# BUTTONs.net
KiCad netlist of a schematic drawn in Altium Designer
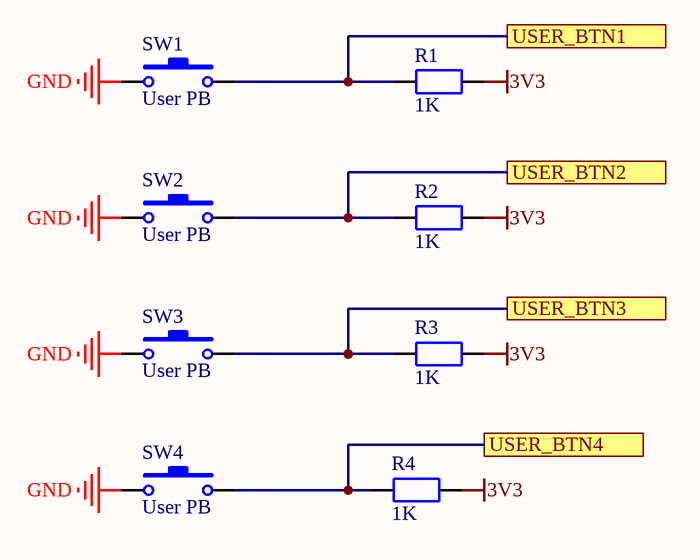
[diagram p0: BUTTONs.SchDoc]

(export (version "E")
  (design (tool "Eeschema 10.0.6"))
  (components
    (comp (ref "R1")
      (value "1K")
      (footprint "0402_RES")
      (description "Resistor")
      (libsource (lib "Lib3D_Altium10_Schlib") (part "RES"))
    )
    (comp (ref "R2")
      (value "1K")
      (footprint "0402_RES")
      (description "Resistor")
      (libsource (lib "Lib3D_Altium10_Schlib") (part "RES"))
    )
    (comp (ref "R3")
      (value "1K")
      (footprint "0402_RES")
      (description "Resistor")
      (libsource (lib "Lib3D_Altium10_Schlib") (part "RES"))
    )
    (comp (ref "R4")
      (value "1K")
      (footprint "0402_RES")
      (description "Resistor")
      (libsource (lib "Lib3D_Altium10_Schlib") (part "RES"))
    )
    (comp (ref "SW1")
      (value "User PB")
      (footprint "SW-PB SMD KMR2")
      (description "Push-button SMD")
      (libsource (lib "ST_Lib3D") (part "SW-PB_1"))
    )
    (comp (ref "SW2")
      (value "User PB")
      (footprint "SW-PB SMD KMR2")
      (description "Push-button SMD")
      (libsource (lib "ST_Lib3D") (part "SW-PB_1"))
    )
    (comp (ref "SW3")
      (value "User PB")
      (footprint "SW-PB SMD KMR2")
      (description "Push-button SMD")
      (libsource (lib "ST_Lib3D") (part "SW-PB_1"))
    )
    (comp (ref "SW4")
      (value "User PB")
      (footprint "SW-PB SMD KMR2")
      (description "Push-button SMD")
      (libsource (lib "ST_Lib3D") (part "SW-PB_1"))
    )
  )
  (nets
    (net (code "1") (name "/USER_BTN1") (class "Default")
      (node (ref "R1") (pin "1") (pinfunction "1_1") (pintype "passive"))
      (node (ref "SW1") (pin "2") (pinfunction "2_2") (pintype "passive"))
    )
    (net (code "2") (name "/USER_BTN2") (class "Default")
      (node (ref "R2") (pin "1") (pinfunction "1_1") (pintype "passive"))
      (node (ref "SW2") (pin "2") (pinfunction "2_2") (pintype "passive"))
    )
    (net (code "3") (name "/USER_BTN3") (class "Default")
      (node (ref "R3") (pin "1") (pinfunction "1_1") (pintype "passive"))
      (node (ref "SW3") (pin "2") (pinfunction "2_2") (pintype "passive"))
    )
    (net (code "4") (name "/USER_BTN4") (class "Default")
      (node (ref "R4") (pin "1") (pinfunction "1_1") (pintype "passive"))
      (node (ref "SW4") (pin "2") (pinfunction "2_2") (pintype "passive"))
    )
    (net (code "5") (name "3V3") (class "Default")
      (node (ref "R1") (pin "2") (pinfunction "2_2") (pintype "passive"))
      (node (ref "R2") (pin "2") (pinfunction "2_2") (pintype "passive"))
      (node (ref "R3") (pin "2") (pinfunction "2_2") (pintype "passive"))
      (node (ref "R4") (pin "2") (pinfunction "2_2") (pintype "passive"))
    )
    (net (code "6") (name "GND") (class "Default")
      (node (ref "SW1") (pin "1") (pinfunction "1_1") (pintype "passive"))
      (node (ref "SW2") (pin "1") (pinfunction "1_1") (pintype "passive"))
      (node (ref "SW3") (pin "1") (pinfunction "1_1") (pintype "passive"))
      (node (ref "SW4") (pin "1") (pinfunction "1_1") (pintype "passive"))
    )
  )
)
